# perimeter_sensor.net
KiCad netlist of a schematic drawn in EAGLE
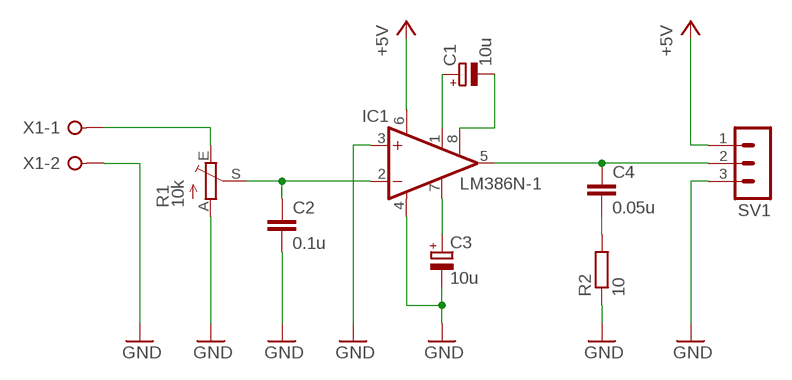
[diagram p0: schematic, sheet 1]

(export (version "E")
  (design (tool "Eeschema 10.0.6"))
  (components
    (comp (ref "C1")
      (value "10u")
      (footprint "eagle-import:E2,5-6")
      (libsource (lib "eagle-import") (part "CPOL-EUE2.5-6"))
    )
    (comp (ref "C2")
      (value "0.1u")
      (footprint "eagle-import:C050-025X075")
      (libsource (lib "eagle-import") (part "C-EU050-025X075"))
    )
    (comp (ref "C3")
      (value "10u")
      (footprint "eagle-import:E2,5-6")
      (libsource (lib "eagle-import") (part "CPOL-EUE2.5-6"))
    )
    (comp (ref "C4")
      (value "0.05u")
      (footprint "eagle-import:C050-025X075")
      (libsource (lib "eagle-import") (part "C-EU050-025X075"))
    )
    (comp (ref "IC1")
      (value "LM386N-1")
      (footprint "eagle-import:DIL08")
      (libsource (lib "eagle-import") (part "LM386?-N1"))
    )
    (comp (ref "R1")
      (value "10k")
      (footprint "eagle-import:S64W")
      (libsource (lib "eagle-import") (part "TRIM_EU-S64W"))
    )
    (comp (ref "R2")
      (value "10")
      (footprint "eagle-import:0204_7")
      (libsource (lib "eagle-import") (part "R-EU_0204/7"))
    )
    (comp (ref "SV1")
      (value "MA03-1")
      (footprint "eagle-import:MA03-1")
      (libsource (lib "eagle-import") (part "MA03-1"))
    )
    (comp (ref "X1")
      (value "W237-02P")
      (footprint "eagle-import:W237-132")
      (libsource (lib "eagle-import") (part "W237-02P"))
    )
  )
  (nets
    (net (code "1") (name "+5V") (class "Default")
      (node (ref "IC1") (pin "6") (pinfunction "VS_6") (pintype "power_in"))
      (node (ref "SV1") (pin "1") (pinfunction "1_1") (pintype "passive"))
    )
    (net (code "2") (name "GND") (class "Default")
      (node (ref "C2") (pin "2") (pinfunction "2_2") (pintype "passive"))
      (node (ref "C3") (pin "-") (pinfunction "-_-") (pintype "passive"))
      (node (ref "IC1") (pin "3") (pinfunction "+IN_3") (pintype "input"))
      (node (ref "IC1") (pin "4") (pinfunction "GND_4") (pintype "power_in"))
      (node (ref "R1") (pin "A") (pinfunction "A_A") (pintype "passive"))
      (node (ref "R2") (pin "1") (pinfunction "1_1") (pintype "passive"))
      (node (ref "SV1") (pin "3") (pinfunction "3_3") (pintype "passive"))
      (node (ref "X1") (pin "2") (pinfunction "KL_2") (pintype "passive"))
    )
    (net (code "3") (name "Net-(C1-Pad+)") (class "Default")
      (node (ref "C1") (pin "+") (pinfunction "+_+") (pintype "passive"))
      (node (ref "IC1") (pin "1") (pinfunction "GAIN_1") (pintype "passive"))
    )
    (net (code "4") (name "Net-(C1-Pad-)") (class "Default")
      (node (ref "C1") (pin "-") (pinfunction "-_-") (pintype "passive"))
      (node (ref "IC1") (pin "8") (pinfunction "GAIN_8") (pintype "passive"))
    )
    (net (code "5") (name "Net-(C4-Pad2)") (class "Default")
      (node (ref "C4") (pin "2") (pinfunction "2_2") (pintype "passive"))
      (node (ref "R2") (pin "2") (pinfunction "2_2") (pintype "passive"))
    )
    (net (code "6") (name "Net-(IC1--IN)") (class "Default")
      (node (ref "C2") (pin "1") (pinfunction "1_1") (pintype "passive"))
      (node (ref "IC1") (pin "2") (pinfunction "-IN_2") (pintype "input"))
      (node (ref "R1") (pin "S") (pinfunction "S_S") (pintype "passive"))
    )
    (net (code "7") (name "Net-(IC1-BYPASS)") (class "Default")
      (node (ref "C3") (pin "+") (pinfunction "+_+") (pintype "passive"))
      (node (ref "IC1") (pin "7") (pinfunction "BYPASS_7") (pintype "passive"))
    )
    (net (code "8") (name "Net-(IC1-OUT)") (class "Default")
      (node (ref "C4") (pin "1") (pinfunction "1_1") (pintype "passive"))
      (node (ref "IC1") (pin "5") (pinfunction "OUT_5") (pintype "output"))
      (node (ref "SV1") (pin "2") (pinfunction "2_2") (pintype "passive"))
    )
    (net (code "9") (name "Net-(X1A-KL)") (class "Default")
      (node (ref "R1") (pin "E") (pinfunction "E_E") (pintype "passive"))
      (node (ref "X1") (pin "1") (pinfunction "KL_1") (pintype "passive"))
    )
  )
)
